# Tut1.net
KiCad netlist of a schematic drawn in Altium Designer
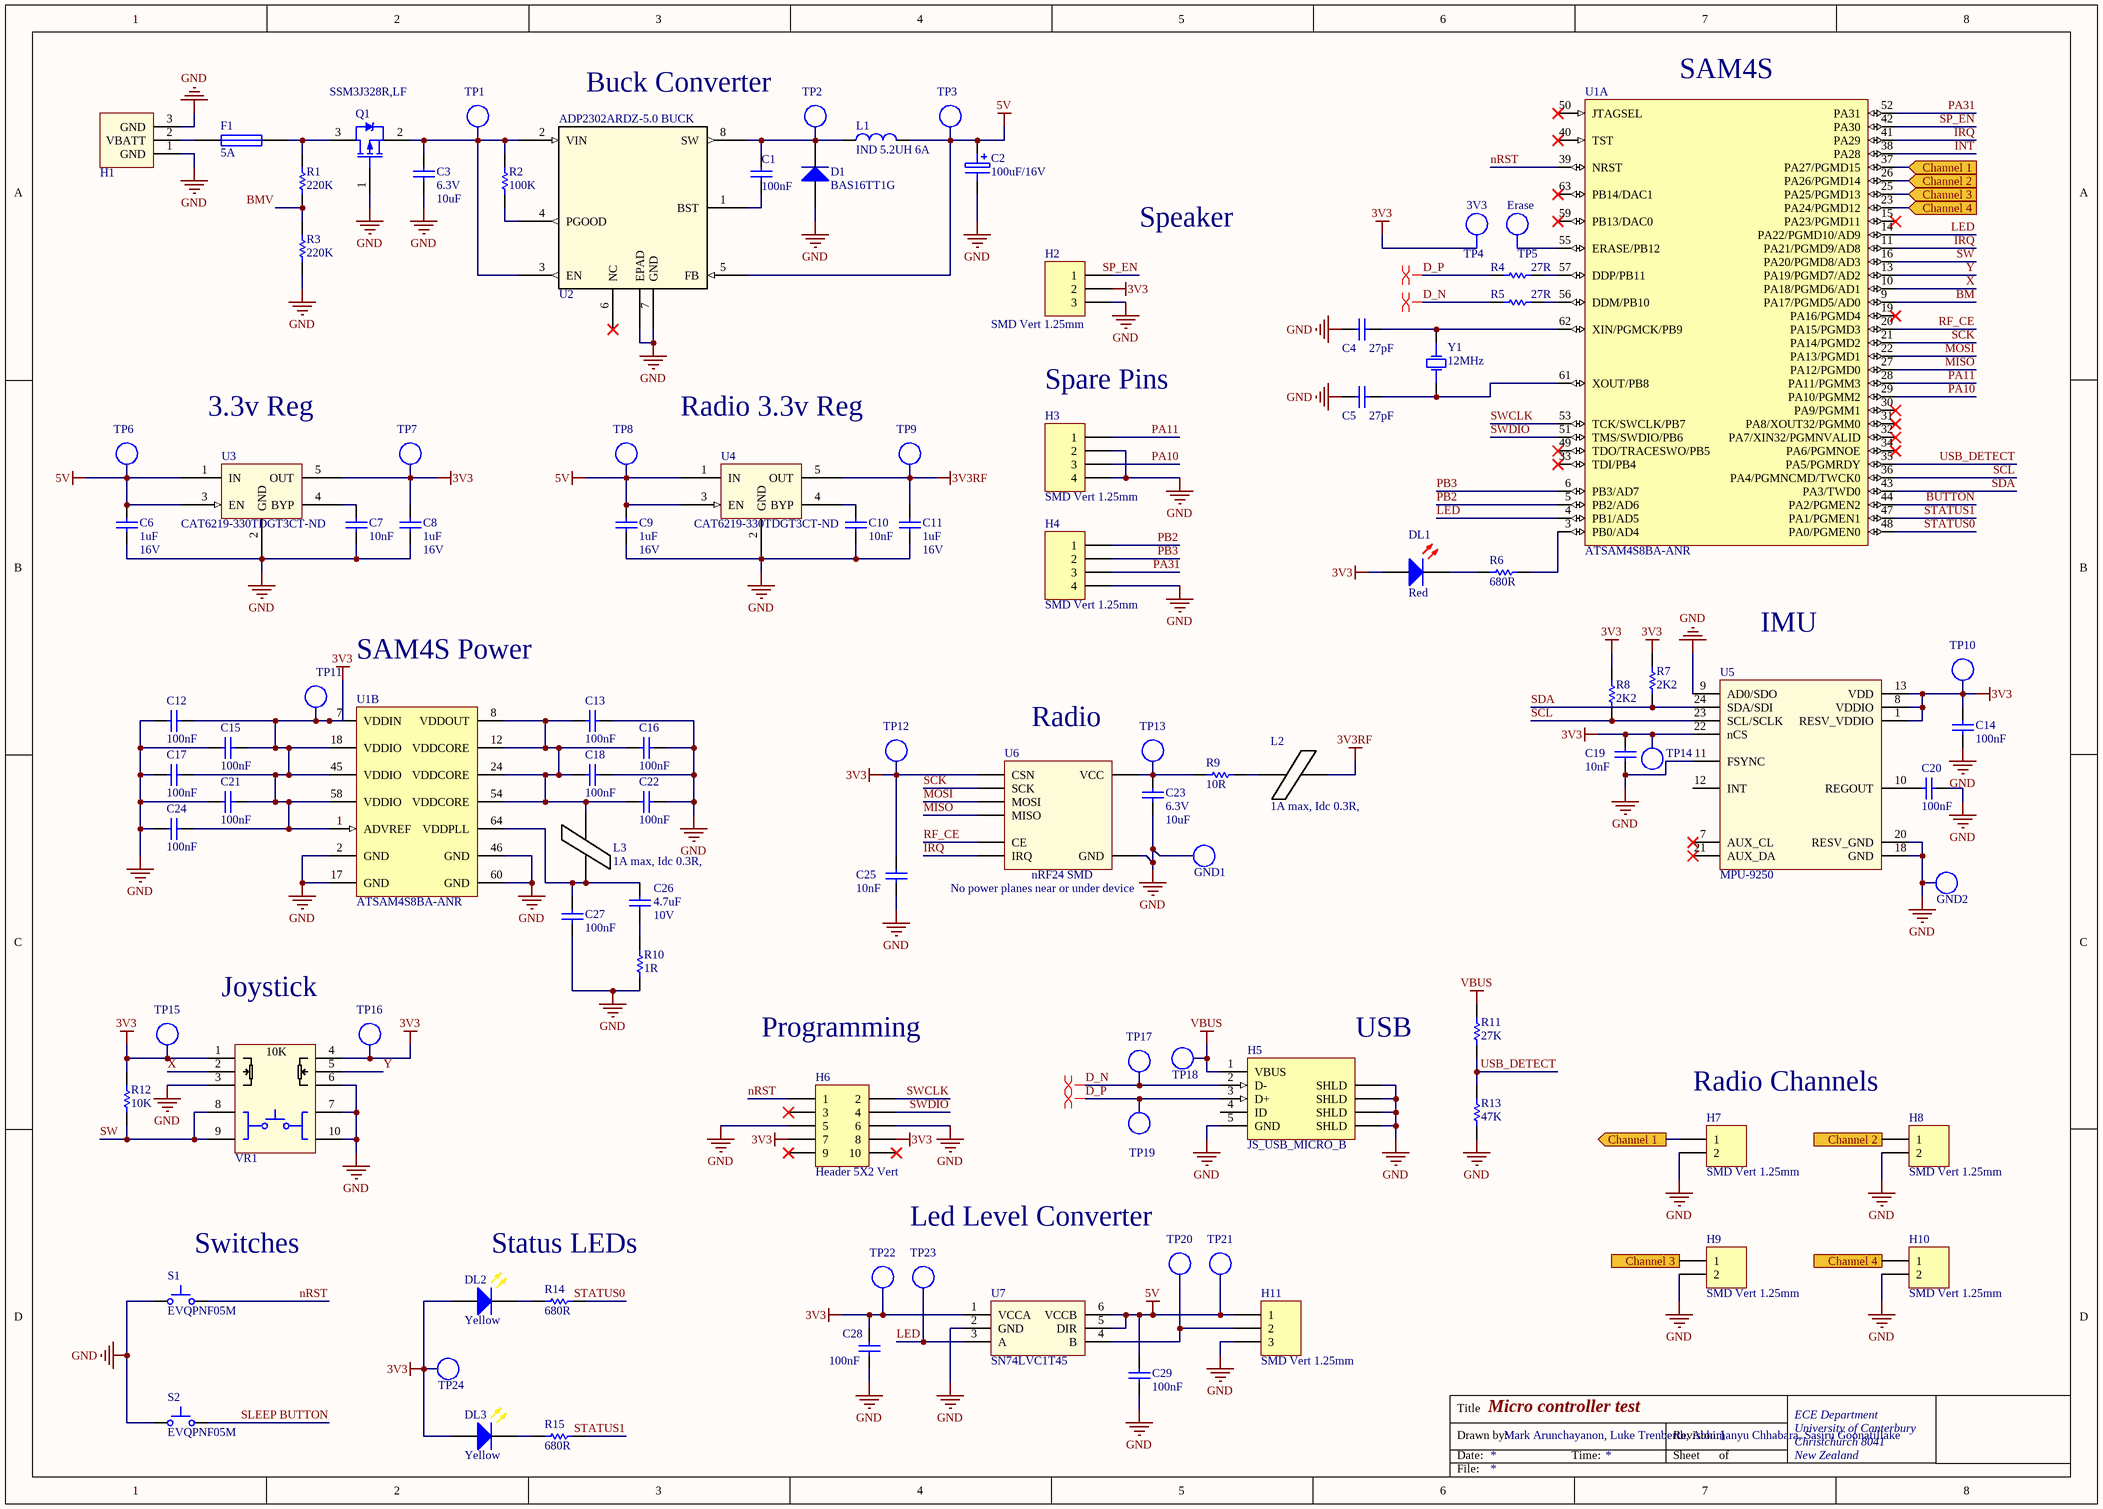
[diagram p0: Tut1.SchDoc]

(export (version "E")
  (design (tool "Eeschema 10.0.6"))
  (components
    (comp (ref "C1")
      (value "100nF")
      (footprint "CAPC1608L")
      (description "CAP CER 100nF X7R +-10% 50V 0603")
      (libsource (lib "ECE AD19Components_19V1") (part "CC_100nF_0603"))
    )
    (comp (ref "C2")
      (value "100uF/16V")
      (footprint "NICH-1")
      (description "CAP ALUM 100uF 16V SMD")
      (fields (field (name "MANUFACTURER") "Nichcon"))
      (libsource (lib "ECE AD19Components_19V1") (part "CA_100uF_16V"))
    )
    (comp (ref "C3")
      (value "10uF")
      (footprint "CAPC1608L")
      (description "CAP CER 10UF X5R +-20% 6V3 0603")
      (fields (field (name "VOLTAGE - RATED") "6.3V"))
      (libsource (lib "ECE AD19Components_19V1") (part "CC_10uF_0603"))
    )
    (comp (ref "C4")
      (value "27pF")
      (footprint "CAPC1608L")
      (description "CAP CER 27pF NPO/COG +-5% 50V 0603")
      (libsource (lib "ECE AD19Components_19V1") (part "CC_27pF_0603"))
    )
    (comp (ref "C5")
      (value "27pF")
      (footprint "CAPC1608L")
      (description "CAP CER 27pF NPO/COG +-5% 50V 0603")
      (libsource (lib "ECE AD19Components_19V1") (part "CC_27pF_0603"))
    )
    (comp (ref "C6")
      (value "1uF")
      (footprint "CAPC1608L")
      (description "CAP CER 1uF Y5V -20% +80% 16V 0603")
      (fields (field (name "MAX VOLTAGE") "16V"))
      (libsource (lib "ECE AD19Components_19V1") (part "CC_1uF_0603"))
    )
    (comp (ref "C7")
      (value "10nF")
      (footprint "CAPC1608L")
      (description "CAP CER 10nF X7R +-10% 50V 0603")
      (libsource (lib "ECE AD19Components_19V1") (part "CC_10nF_0603"))
    )
    (comp (ref "C8")
      (value "1uF")
      (footprint "CAPC1608L")
      (description "CAP CER 1uF Y5V -20% +80% 16V 0603")
      (fields (field (name "MAX VOLTAGE") "16V"))
      (libsource (lib "ECE AD19Components_19V1") (part "CC_1uF_0603"))
    )
    (comp (ref "C9")
      (value "1uF")
      (footprint "CAPC1608L")
      (description "CAP CER 1uF Y5V -20% +80% 16V 0603")
      (fields (field (name "MAX VOLTAGE") "16V"))
      (libsource (lib "ECE AD19Components_19V1") (part "CC_1uF_0603"))
    )
    (comp (ref "C10")
      (value "10nF")
      (footprint "CAPC1608L")
      (description "CAP CER 10nF X7R +-10% 50V 0603")
      (libsource (lib "ECE AD19Components_19V1") (part "CC_10nF_0603"))
    )
    (comp (ref "C11")
      (value "1uF")
      (footprint "CAPC1608L")
      (description "CAP CER 1uF Y5V -20% +80% 16V 0603")
      (fields (field (name "MAX VOLTAGE") "16V"))
      (libsource (lib "ECE AD19Components_19V1") (part "CC_1uF_0603"))
    )
    (comp (ref "C12")
      (value "100nF")
      (footprint "CAPC1608L")
      (description "CAP CER 100nF X7R +-10% 50V 0603")
      (libsource (lib "ECE AD19Components_19V1") (part "CC_100nF_0603"))
    )
    (comp (ref "C13")
      (value "100nF")
      (footprint "CAPC1608L")
      (description "CAP CER 100nF X7R +-10% 50V 0603")
      (libsource (lib "ECE AD19Components_19V1") (part "CC_100nF_0603"))
    )
    (comp (ref "C14")
      (value "100nF")
      (footprint "CAPC1608L")
      (description "CAP CER 100nF X7R +-10% 50V 0603")
      (libsource (lib "ECE AD19Components_19V1") (part "CC_100nF_0603"))
    )
    (comp (ref "C15")
      (value "100nF")
      (footprint "CAPC1608L")
      (description "CAP CER 100nF X7R +-10% 50V 0603")
      (libsource (lib "ECE AD19Components_19V1") (part "CC_100nF_0603"))
    )
    (comp (ref "C16")
      (value "100nF")
      (footprint "CAPC1608L")
      (description "CAP CER 100nF X7R +-10% 50V 0603")
      (libsource (lib "ECE AD19Components_19V1") (part "CC_100nF_0603"))
    )
    (comp (ref "C17")
      (value "100nF")
      (footprint "CAPC1608L")
      (description "CAP CER 100nF X7R +-10% 50V 0603")
      (libsource (lib "ECE AD19Components_19V1") (part "CC_100nF_0603"))
    )
    (comp (ref "C18")
      (value "100nF")
      (footprint "CAPC1608L")
      (description "CAP CER 100nF X7R +-10% 50V 0603")
      (libsource (lib "ECE AD19Components_19V1") (part "CC_100nF_0603"))
    )
    (comp (ref "C19")
      (value "10nF")
      (footprint "CAPC1608L")
      (description "CAP CER 10nF X7R +-10% 50V 0603")
      (libsource (lib "ECE AD19Components_19V1") (part "CC_10nF_0603"))
    )
    (comp (ref "C20")
      (value "100nF")
      (footprint "CAPC1608L")
      (description "CAP CER 100nF X7R +-10% 50V 0603")
      (libsource (lib "ECE AD19Components_19V1") (part "CC_100nF_0603"))
    )
    (comp (ref "C21")
      (value "100nF")
      (footprint "CAPC1608L")
      (description "CAP CER 100nF X7R +-10% 50V 0603")
      (libsource (lib "ECE AD19Components_19V1") (part "CC_100nF_0603"))
    )
    (comp (ref "C22")
      (value "100nF")
      (footprint "CAPC1608L")
      (description "CAP CER 100nF X7R +-10% 50V 0603")
      (libsource (lib "ECE AD19Components_19V1") (part "CC_100nF_0603"))
    )
    (comp (ref "C23")
      (value "10uF")
      (footprint "CAPC1608L")
      (description "CAP CER 10UF X5R +-20% 6V3 0603")
      (fields (field (name "VOLTAGE - RATED") "6.3V"))
      (libsource (lib "ECE AD19Components_19V1") (part "CC_10uF_0603"))
    )
    (comp (ref "C24")
      (value "100nF")
      (footprint "CAPC1608L")
      (description "CAP CER 100nF X7R +-10% 50V 0603")
      (libsource (lib "ECE AD19Components_19V1") (part "CC_100nF_0603"))
    )
    (comp (ref "C25")
      (value "10nF")
      (footprint "CAPC1608L")
      (description "CAP CER 10nF X7R +-10% 50V 0603")
      (libsource (lib "ECE AD19Components_19V1") (part "CC_10nF_0603"))
    )
    (comp (ref "C26")
      (value "4.7uF")
      (footprint "CAPC1608N")
      (description "CAP CER 4.7uF X5R +-20%  10V 0603")
      (fields (field (name "MAX VOLTAGE") "10V"))
      (libsource (lib "ECE AD19Components_19V1") (part "CC_4.7uF_0603"))
    )
    (comp (ref "C27")
      (value "100nF")
      (footprint "CAPC1608L")
      (description "CAP CER 100nF X7R +-10% 50V 0603")
      (libsource (lib "ECE AD19Components_19V1") (part "CC_100nF_0603"))
    )
    (comp (ref "C28")
      (value "100nF")
      (footprint "CAPC1608L")
      (description "CAP CER 100nF X7R +-10% 50V 0603")
      (libsource (lib "ECE AD19Components_19V1") (part "CC_100nF_0603"))
    )
    (comp (ref "C29")
      (value "100nF")
      (footprint "CAPC1608L")
      (description "CAP CER 100nF X7R +-10% 50V 0603")
      (libsource (lib "ECE AD19Components_19V1") (part "CC_100nF_0603"))
    )
    (comp (ref "D1")
      (value "BAS16TT1G")
      (footprint "SOT416")
      (description "Diode Switching, Vr 75V, 200mA, SOT-416")
      (fields (field (name "MANUFACTURER") "ON Semiconductor"))
      (libsource (lib "ECE AD19Components_19V1") (part "DR_BAS16TT1G"))
    )
    (comp (ref "DL1")
      (value "Red")
      (footprint "WL-SMCW0603")
      (description "LED Red 250mcd 0603 SMD")
      (fields
        (field (name "MANUFACTURER") "WURTH ELEKTRONIK")
        (field (name "MANUFACTURER PART NUMBER") "150060RS75000")
        (field (name "LED COLOUR") "Red")
      )
      (libsource (lib "ECE AD19Components_19V1") (part "DL_150060RS75000"))
    )
    (comp (ref "DL2")
      (value "Yellow")
      (footprint "WL-SMCW0603")
      (description "LED Yellow 120mcd 0603 SMD")
      (fields
        (field (name "MANUFACTURER") "WURTH ELEKTRONIK")
        (field (name "MANUFACTURER PART NUMBER") "150060YS75000")
        (field (name "LED COLOUR") "Yellow")
      )
      (libsource (lib "ECE AD19Components_19V1") (part "DL_150060YS75000"))
    )
    (comp (ref "DL3")
      (value "Yellow")
      (footprint "WL-SMCW0603")
      (description "LED Yellow 120mcd 0603 SMD")
      (fields
        (field (name "MANUFACTURER") "WURTH ELEKTRONIK")
        (field (name "MANUFACTURER PART NUMBER") "150060YS75000")
        (field (name "LED COLOUR") "Yellow")
      )
      (libsource (lib "ECE AD19Components_19V1") (part "DL_150060YS75000"))
    )
    (comp (ref "F1")
      (value "5A")
      (footprint "RESC3216N")
      (description "Fuse 5.0A Fast Acting 1206 SMD")
      (fields (field (name "MANUFACTURER PART NUMBER") "C1F5") (field (name "MANUFACTURER") "Bel TRP"))
      (libsource (lib "ECE AD19Components_19V1") (part "FS_Fuse_5.0A"))
    )
    (comp (ref "GND1")
      (value "TP_0603")
      (footprint "TP_0603")
      (description "Test Point 1.65X0.9X1.2mm SMD")
      (fields
        (field (name "MANUFACTURER") "TE Connectivity AMP Connectors")
        (field (name "MANUFACTURER PART NUMBER") "1625854-3")
      )
      (libsource (lib "ECE AD19Components_19V1") (part "TP_0603"))
    )
    (comp (ref "GND2")
      (value "TP_0603")
      (footprint "TP_0603")
      (description "Test Point 1.65X0.9X1.2mm SMD")
      (fields
        (field (name "MANUFACTURER") "TE Connectivity AMP Connectors")
        (field (name "MANUFACTURER PART NUMBER") "1625854-3")
      )
      (libsource (lib "ECE AD19Components_19V1") (part "TP_0603"))
    )
    (comp (ref "H1")
      (value "Battery_HEADER_3pin")
      (footprint "BATT_HEADER_3POS")
      (description "3Pin Header 2.54mm spacing")
      (libsource (lib "ENCE461AD19_19V2") (part "Battery_HEADER_3pin"))
    )
    (comp (ref "H2")
      (value "SMD Vert 1.25mm")
      (footprint "SD-53398-0319")
      (description "Header_Vert_3Pos_1.25mm_125V@1A_SMT")
      (fields (field (name "MANUFACTURER") "MOLEX") (field (name "MANUFACTURER PART NUMBER") "53398-0371"))
      (libsource (lib "ECE AD19Components_19V1") (part "JB_53398-03"))
    )
    (comp (ref "H3")
      (value "SMD Vert 1.25mm")
      (footprint "SD-53398-0419")
      (description "Header_Vert_4Pos_1.25mm_125V@1A_SMT")
      (fields (field (name "MANUFACTURER") "MOLEX") (field (name "MANUFACTURER PART NUMBER") "53398-0471"))
      (libsource (lib "ECE AD19Components_19V1") (part "JB_53398-04"))
    )
    (comp (ref "H4")
      (value "SMD Vert 1.25mm")
      (footprint "SD-53398-0419")
      (description "Header_Vert_4Pos_1.25mm_125V@1A_SMT")
      (fields (field (name "MANUFACTURER") "MOLEX") (field (name "MANUFACTURER PART NUMBER") "53398-0471"))
      (libsource (lib "ECE AD19Components_19V1") (part "JB_53398-04"))
    )
    (comp (ref "H5")
      (value "JS_USB_MICRO_B")
      (footprint "FCI_USB_10118194-0001LF")
      (description "CONN USB MICRO B RECPT SMT R/A")
      (fields (field (name "MANUFACTURER") "FCI") (field (name "MANUFACTURER PART NUMBER") "10118194-0001LF"))
      (libsource (lib "ECE AD19Components_19V1") (part "JS_USB_MICRO_B_SMT"))
    )
    (comp (ref "H6")
      (value "Header 5X2 Vert")
      (footprint "IDC2.54-V10D")
      (description "IDC Header, 2,54mm, 10-Pin, Vert")
      (libsource (lib "ECE AD19Components_19V1") (part "JA_HDR_IDC_5X2_VERT"))
    )
    (comp (ref "H7")
      (value "SMD Vert 1.25mm")
      (footprint "SD-53398-0219")
      (description "Header_Vert_2Pos_1.25mm_125V@1A_SMT")
      (fields
        (field (name "MANUFACTURER") "Molex Inc")
        (field (name "MANUFACTURER PART NUMBER") "0533980271")
      )
      (libsource (lib "ECE AD19Components_19V1") (part "JB_53398-02"))
    )
    (comp (ref "H8")
      (value "SMD Vert 1.25mm")
      (footprint "SD-53398-0219")
      (description "Header_Vert_2Pos_1.25mm_125V@1A_SMT")
      (fields
        (field (name "MANUFACTURER") "Molex Inc")
        (field (name "MANUFACTURER PART NUMBER") "0533980271")
      )
      (libsource (lib "ECE AD19Components_19V1") (part "JB_53398-02"))
    )
    (comp (ref "H9")
      (value "SMD Vert 1.25mm")
      (footprint "SD-53398-0219")
      (description "Header_Vert_2Pos_1.25mm_125V@1A_SMT")
      (fields
        (field (name "MANUFACTURER") "Molex Inc")
        (field (name "MANUFACTURER PART NUMBER") "0533980271")
      )
      (libsource (lib "ECE AD19Components_19V1") (part "JB_53398-02"))
    )
    (comp (ref "H10")
      (value "SMD Vert 1.25mm")
      (footprint "SD-53398-0219")
      (description "Header_Vert_2Pos_1.25mm_125V@1A_SMT")
      (fields
        (field (name "MANUFACTURER") "Molex Inc")
        (field (name "MANUFACTURER PART NUMBER") "0533980271")
      )
      (libsource (lib "ECE AD19Components_19V1") (part "JB_53398-02"))
    )
    (comp (ref "H11")
      (value "SMD Vert 1.25mm")
      (footprint "SD-53398-0319")
      (description "Header_Vert_3Pos_1.25mm_125V@1A_SMT")
      (fields (field (name "MANUFACTURER") "MOLEX") (field (name "MANUFACTURER PART NUMBER") "53398-0371"))
      (libsource (lib "") (part "JB_53398-03_1"))
    )
    (comp (ref "L1")
      (value "IND 5.2UH 6A")
      (footprint "INDUCTOR5u2")
      (description "FIXED IND 5.2UH 6A 22 MOHM SMD")
      (fields
        (field (name "MANUFACTURER") "Sumida America Components Inc.")
        (field (name "MANUFACTURER PART NUMBER") "CDRH104RNP-5R2NC")
      )
      (libsource (lib "ENCE461AD19_19V2") (part "CDRH104RNP-5R2NC"))
    )
    (comp (ref "L2")
      (value "1A max, Idc 0.3R,")
      (footprint "INDC3216L")
      (description "Ferrite Bead, Rdc 0.3R, Z100MHZ 600R, Imax 1A, SMD 1206")
      (fields
        (field (name "MANUFACTURER") "FAIR-RITE")
        (field (name "MANUFACTURER PART NUMBER") "2512066017Y1")
      )
      (libsource (lib "ECE AD19Components_19V1") (part "IN_Ferrite-Bead"))
    )
    (comp (ref "L3")
      (value "1A max, Idc 0.3R,")
      (footprint "INDC3216L")
      (description "Ferrite Bead, Rdc 0.3R, Z100MHZ 600R, Imax 1A, SMD 1206")
      (fields
        (field (name "MANUFACTURER") "FAIR-RITE")
        (field (name "MANUFACTURER PART NUMBER") "2512066017Y1")
      )
      (libsource (lib "ECE AD19Components_19V1") (part "IN_Ferrite-Bead"))
    )
    (comp (ref "Q1")
      (value "SSM3J328R,LF")
      (footprint "SOT23_L")
      (description "MOSFET P-CH 20V 6A SOT23-3")
      (fields
        (field (name "MANUFACTURER") "Toshiba")
        (field (name "MANUFACTURER PART NUMBER") "SSM3J328R,LF")
      )
      (libsource (lib "ECE AD19Components_19V1") (part "TM_SSM3J328R"))
    )
    (comp (ref "R1")
      (value "220K")
      (footprint "RESC1608L")
      (description "RES 3.3K OHM 1/10W 5% 0603 SMD")
      (libsource (lib "ECE AD19Components_19V1") (part "RS_220K"))
    )
    (comp (ref "R2")
      (value "100K")
      (footprint "RESC1608L")
      (description "RES 100K OHM 1/10W 5% 0603 SMD")
      (libsource (lib "ECE AD19Components_19V1") (part "RS_100K"))
    )
    (comp (ref "R3")
      (value "220K")
      (footprint "RESC1608L")
      (description "RES 3.3K OHM 1/10W 5% 0603 SMD")
      (libsource (lib "ECE AD19Components_19V1") (part "RS_220K"))
    )
    (comp (ref "R4")
      (value "27R")
      (footprint "RESC3216L")
      (description "RES 27R OHM 1/4W 5% 1206 SMD")
      (libsource (lib "ECE AD19Components_19V1") (part "RT_27R"))
    )
    (comp (ref "R5")
      (value "27R")
      (footprint "RESC3216L")
      (description "RES 27R OHM 1/4W 5% 1206 SMD")
      (libsource (lib "ECE AD19Components_19V1") (part "RT_27R"))
    )
    (comp (ref "R6")
      (value "680R")
      (footprint "RESC1608L")
      (description "RES 680 OHM 1/10W 5% 0603 SMD")
      (libsource (lib "ECE AD19Components_19V1") (part "RS_680R"))
    )
    (comp (ref "R7")
      (value "2K2")
      (footprint "RESC1608L")
      (description "RES 2.2K OHM 1/10W 5% 0603 SMD")
      (libsource (lib "ECE AD19Components_19V1") (part "RS_2K2"))
    )
    (comp (ref "R8")
      (value "2K2")
      (footprint "RESC1608L")
      (description "RES 2.2K OHM 1/10W 5% 0603 SMD")
      (libsource (lib "ECE AD19Components_19V1") (part "RS_2K2"))
    )
    (comp (ref "R9")
      (value "10R")
      (footprint "RESC1608L")
      (description "RES 10 OHM 1/10W 5% 0603 SMD")
      (libsource (lib "ECE AD19Components_19V1") (part "RS_10R"))
    )
    (comp (ref "R10")
      (value "1R")
      (footprint "RESC3216L")
      (description "RES 1R OHM 1/4W 5% 1206 SMD")
      (libsource (lib "ECE AD19Components_19V1") (part "RT_1R"))
    )
    (comp (ref "R11")
      (value "27K")
      (footprint "RESC1608L")
      (description "RES 27K OHM 1/10W 5% 0603 SMD")
      (libsource (lib "ECE AD19Components_19V1") (part "RS_27K"))
    )
    (comp (ref "R12")
      (value "10K")
      (footprint "RESC1608L")
      (description "RES 10.0K OHM 1/10W 5% 0603 SMD")
      (libsource (lib "ECE AD19Components_19V1") (part "RS_10K"))
    )
    (comp (ref "R13")
      (value "47K")
      (footprint "RESC1608N")
      (description "RES 47.0K OHM 1/10W 5% 0603 SMD")
      (libsource (lib "ECE AD19Components_19V1") (part "RS_47K"))
    )
    (comp (ref "R14")
      (value "680R")
      (footprint "RESC1608L")
      (description "RES 680 OHM 1/10W 5% 0603 SMD")
      (libsource (lib "ECE AD19Components_19V1") (part "RS_680R"))
    )
    (comp (ref "R15")
      (value "680R")
      (footprint "RESC1608L")
      (description "RES 680 OHM 1/10W 5% 0603 SMD")
      (libsource (lib "ECE AD19Components_19V1") (part "RS_680R"))
    )
    (comp (ref "S1")
      (value "EVQPNF05M")
      (footprint "EVQPNF05M")
      (description "Panasonic 6 x 3.5mm SMD Light Touch Switch Type SMD")
      (fields (field (name "MANUFACTURER") "Panasonic"))
      (libsource (lib "ECE AD19Components_19V1") (part "WS_EVQPNF05M"))
    )
    (comp (ref "S2")
      (value "EVQPNF05M")
      (footprint "EVQPNF05M")
      (description "Panasonic 6 x 3.5mm SMD Light Touch Switch Type SMD")
      (fields (field (name "MANUFACTURER") "Panasonic"))
      (libsource (lib "ECE AD19Components_19V1") (part "WS_EVQPNF05M"))
    )
    (comp (ref "TP1")
      (value "TP_0603")
      (footprint "TP_0603")
      (description "Test Point 1.65X0.9X1.2mm SMD")
      (fields
        (field (name "MANUFACTURER") "TE Connectivity AMP Connectors")
        (field (name "MANUFACTURER PART NUMBER") "1625854-3")
      )
      (libsource (lib "ECE AD19Components_19V1") (part "TP_0603"))
    )
    (comp (ref "TP2")
      (value "TP_0603")
      (footprint "TP_0603")
      (description "Test Point 1.65X0.9X1.2mm SMD")
      (fields
        (field (name "MANUFACTURER") "TE Connectivity AMP Connectors")
        (field (name "MANUFACTURER PART NUMBER") "1625854-3")
      )
      (libsource (lib "ECE AD19Components_19V1") (part "TP_0603"))
    )
    (comp (ref "TP3")
      (value "TP_0603")
      (footprint "TP_0603")
      (description "Test Point 1.65X0.9X1.2mm SMD")
      (fields
        (field (name "MANUFACTURER") "TE Connectivity AMP Connectors")
        (field (name "MANUFACTURER PART NUMBER") "1625854-3")
      )
      (libsource (lib "ECE AD19Components_19V1") (part "TP_0603"))
    )
    (comp (ref "TP4")
      (value "3V3")
      (footprint "TP_1206")
      (description "Test-Point 3.3x1.6x2.1mm SMD")
      (fields
        (field (name "MANUFACTURER") "Harwin Inc")
        (field (name "MANUFACTURER PART NUMBER") "S1751-46R")
      )
      (libsource (lib "ECE AD19Components_19V1") (part "TP_1206"))
    )
    (comp (ref "TP5")
      (value "Erase")
      (footprint "TP_1206")
      (description "Test-Point 3.3x1.6x2.1mm SMD")
      (fields
        (field (name "MANUFACTURER") "Harwin Inc")
        (field (name "MANUFACTURER PART NUMBER") "S1751-46R")
      )
      (libsource (lib "ECE AD19Components_19V1") (part "TP_1206"))
    )
    (comp (ref "TP6")
      (value "TP_0603")
      (footprint "TP_0603")
      (description "Test Point 1.65X0.9X1.2mm SMD")
      (fields
        (field (name "MANUFACTURER") "TE Connectivity AMP Connectors")
        (field (name "MANUFACTURER PART NUMBER") "1625854-3")
      )
      (libsource (lib "ECE AD19Components_19V1") (part "TP_0603"))
    )
    (comp (ref "TP7")
      (value "TP_0603")
      (footprint "TP_0603")
      (description "Test Point 1.65X0.9X1.2mm SMD")
      (fields
        (field (name "MANUFACTURER") "TE Connectivity AMP Connectors")
        (field (name "MANUFACTURER PART NUMBER") "1625854-3")
      )
      (libsource (lib "ECE AD19Components_19V1") (part "TP_0603"))
    )
    (comp (ref "TP8")
      (value "TP_0603")
      (footprint "TP_0603")
      (description "Test Point 1.65X0.9X1.2mm SMD")
      (fields
        (field (name "MANUFACTURER") "TE Connectivity AMP Connectors")
        (field (name "MANUFACTURER PART NUMBER") "1625854-3")
      )
      (libsource (lib "ECE AD19Components_19V1") (part "TP_0603"))
    )
    (comp (ref "TP9")
      (value "TP_0603")
      (footprint "TP_0603")
      (description "Test Point 1.65X0.9X1.2mm SMD")
      (fields
        (field (name "MANUFACTURER") "TE Connectivity AMP Connectors")
        (field (name "MANUFACTURER PART NUMBER") "1625854-3")
      )
      (libsource (lib "ECE AD19Components_19V1") (part "TP_0603"))
    )
    (comp (ref "TP10")
      (value "TP_0603")
      (footprint "TP_0603")
      (description "Test Point 1.65X0.9X1.2mm SMD")
      (fields
        (field (name "MANUFACTURER") "TE Connectivity AMP Connectors")
        (field (name "MANUFACTURER PART NUMBER") "1625854-3")
      )
      (libsource (lib "ECE AD19Components_19V1") (part "TP_0603"))
    )
    (comp (ref "TP11")
      (value "TP_0603")
      (footprint "TP_0603")
      (description "Test Point 1.65X0.9X1.2mm SMD")
      (fields
        (field (name "MANUFACTURER") "TE Connectivity AMP Connectors")
        (field (name "MANUFACTURER PART NUMBER") "1625854-3")
      )
      (libsource (lib "ECE AD19Components_19V1") (part "TP_0603"))
    )
    (comp (ref "TP12")
      (value "TP_0603")
      (footprint "TP_0603")
      (description "Test Point 1.65X0.9X1.2mm SMD")
      (fields
        (field (name "MANUFACTURER") "TE Connectivity AMP Connectors")
        (field (name "MANUFACTURER PART NUMBER") "1625854-3")
      )
      (libsource (lib "ECE AD19Components_19V1") (part "TP_0603"))
    )
    (comp (ref "TP13")
      (value "TP_0603")
      (footprint "TP_0603")
      (description "Test Point 1.65X0.9X1.2mm SMD")
      (fields
        (field (name "MANUFACTURER") "TE Connectivity AMP Connectors")
        (field (name "MANUFACTURER PART NUMBER") "1625854-3")
      )
      (libsource (lib "ECE AD19Components_19V1") (part "TP_0603"))
    )
    (comp (ref "TP14")
      (value "TP_0603")
      (footprint "TP_0603")
      (description "Test Point 1.65X0.9X1.2mm SMD")
      (fields
        (field (name "MANUFACTURER") "TE Connectivity AMP Connectors")
        (field (name "MANUFACTURER PART NUMBER") "1625854-3")
      )
      (libsource (lib "ECE AD19Components_19V1") (part "TP_0603"))
    )
    (comp (ref "TP15")
      (value "TP_0603")
      (footprint "TP_0603")
      (description "Test Point 1.65X0.9X1.2mm SMD")
      (fields
        (field (name "MANUFACTURER") "TE Connectivity AMP Connectors")
        (field (name "MANUFACTURER PART NUMBER") "1625854-3")
      )
      (libsource (lib "ECE AD19Components_19V1") (part "TP_0603"))
    )
    (comp (ref "TP16")
      (value "TP_0603")
      (footprint "TP_0603")
      (description "Test Point 1.65X0.9X1.2mm SMD")
      (fields
        (field (name "MANUFACTURER") "TE Connectivity AMP Connectors")
        (field (name "MANUFACTURER PART NUMBER") "1625854-3")
      )
      (libsource (lib "ECE AD19Components_19V1") (part "TP_0603"))
    )
    (comp (ref "TP17")
      (value "TP_0603")
      (footprint "TP_0603")
      (description "Test Point 1.65X0.9X1.2mm SMD")
      (fields
        (field (name "MANUFACTURER") "TE Connectivity AMP Connectors")
        (field (name "MANUFACTURER PART NUMBER") "1625854-3")
      )
      (libsource (lib "ECE AD19Components_19V1") (part "TP_0603"))
    )
    (comp (ref "TP18")
      (value "TP_0603")
      (footprint "TP_0603")
      (description "Test Point 1.65X0.9X1.2mm SMD")
      (fields
        (field (name "MANUFACTURER") "TE Connectivity AMP Connectors")
        (field (name "MANUFACTURER PART NUMBER") "1625854-3")
      )
      (libsource (lib "ECE AD19Components_19V1") (part "TP_0603"))
    )
    (comp (ref "TP19")
      (value "TP_0603")
      (footprint "TP_0603")
      (description "Test Point 1.65X0.9X1.2mm SMD")
      (fields
        (field (name "MANUFACTURER") "TE Connectivity AMP Connectors")
        (field (name "MANUFACTURER PART NUMBER") "1625854-3")
      )
      (libsource (lib "ECE AD19Components_19V1") (part "TP_0603"))
    )
    (comp (ref "TP20")
      (value "TP_0603")
      (footprint "TP_0603")
      (description "Test Point 1.65X0.9X1.2mm SMD")
      (fields
        (field (name "MANUFACTURER") "TE Connectivity AMP Connectors")
        (field (name "MANUFACTURER PART NUMBER") "1625854-3")
      )
      (libsource (lib "ECE AD19Components_19V1") (part "TP_0603"))
    )
    (comp (ref "TP21")
      (value "TP_0603")
      (footprint "TP_0603")
      (description "Test Point 1.65X0.9X1.2mm SMD")
      (fields
        (field (name "MANUFACTURER") "TE Connectivity AMP Connectors")
        (field (name "MANUFACTURER PART NUMBER") "1625854-3")
      )
      (libsource (lib "ECE AD19Components_19V1") (part "TP_0603"))
    )
    (comp (ref "TP22")
      (value "TP_0603")
      (footprint "TP_0603")
      (description "Test Point 1.65X0.9X1.2mm SMD")
      (fields
        (field (name "MANUFACTURER") "TE Connectivity AMP Connectors")
        (field (name "MANUFACTURER PART NUMBER") "1625854-3")
      )
      (libsource (lib "ECE AD19Components_19V1") (part "TP_0603"))
    )
    (comp (ref "TP23")
      (value "TP_0603")
      (footprint "TP_0603")
      (description "Test Point 1.65X0.9X1.2mm SMD")
      (fields
        (field (name "MANUFACTURER") "TE Connectivity AMP Connectors")
        (field (name "MANUFACTURER PART NUMBER") "1625854-3")
      )
      (libsource (lib "ECE AD19Components_19V1") (part "TP_0603"))
    )
    (comp (ref "TP24")
      (value "TP_0603")
      (footprint "TP_0603")
      (description "Test Point 1.65X0.9X1.2mm SMD")
      (fields
        (field (name "MANUFACTURER") "TE Connectivity AMP Connectors")
        (field (name "MANUFACTURER PART NUMBER") "1625854-3")
      )
      (libsource (lib "ECE AD19Components_19V1") (part "TP_0603"))
    )
    (comp (ref "U1")
      (value "ATSAM4S8BA-ANR")
      (footprint "LQFP64_L")
      (description "IC MCU 32BIT 512KB FLASH 64LQFP")
      (fields (field (name "MANUFACTURER") "Atmel"))
      (libsource (lib "ECE AD19Components_19V1") (part "SE_ATSAM4S16BA-MU"))
    )
    (comp (ref "U2")
      (value "ADP2302ARDZ-5.0 BUCK")
      (footprint "RD_8_1")
      (description "IC REG BUCK 5V 2A 8SOIC")
      (fields (field (name "MANUFACTURER_PART_NUMBER") "ADP2302ARDZ-5.0-R7"))
      (libsource (lib "ENCE461AD19_19V2") (part "ADP2302ARDZ-5.0-R7"))
    )
    (comp (ref "U3")
      (value "CAT6219-330TDGT3")
      (footprint "SOT95P280X145-5N")
      (description "IC REG LIN 3.3V 500MA TSOT23-5")
      (fields
        (field (name "BASE PART NUMBER") "CAT6219")
        (field (name "SUPPLIER PART NUMBER") "CAT6219-330TDGT3CT-ND")
      )
      (libsource (lib "ENCE461AD19_19V2") (part "SV_CAT6219-330TDGT3"))
    )
    (comp (ref "U4")
      (value "CAT6219-330TDGT3")
      (footprint "SOT95P280X145-5N")
      (description "IC REG LIN 3.3V 500MA TSOT23-5")
      (fields
        (field (name "BASE PART NUMBER") "CAT6219")
        (field (name "SUPPLIER PART NUMBER") "CAT6219-330TDGT3CT-ND")
      )
      (libsource (lib "ENCE461AD19_19V2") (part "SV_CAT6219-330TDGT3"))
    )
    (comp (ref "U5")
      (value "MPU-9250")
      (footprint "Quad24")
      (description "9 axis IMU")
      (libsource (lib "ENCE461AD19_19V2") (part "MPU-9250"))
    )
    (comp (ref "U6")
      (value "nRF24 SMD")
      (footprint "NRF24")
      (description "nRF24 SMD Module")
      (fields (field (name "WARNING") "No power planes near or under device"))
      (libsource (lib "ENCE461AD19_19V2") (part "NRF24"))
    )
    (comp (ref "U7")
      (value "SN74LVC1T45")
      (footprint "SOT23-6_N")
      (description "1.8V - 5V level converter")
      (libsource (lib "ENCE461_extras_2020") (part "SN74LVC1T45"))
    )
    (comp (ref "VR1")
      (value "Joystick 10k with Sw")
      (footprint "Joystick_Sw")
      (description "JOYSTICK 10K OHM 2 AXIS TH")
      (libsource (lib "ENCE461AD19_19V2") (part "Joystick 10k with Sw"))
    )
    (comp (ref "Y1")
      (value "12MHz")
      (footprint "HC49/4h_SMX")
      (description "12.00 MHZ 18PF HC49/4H SMD")
      (fields (field (name "MANUFACTURER") "Abracon Corporation"))
      (libsource (lib "ECE AD19Components_19V1") (part "XT_CRYSTAL_12MHz"))
    )
  )
  (nets
    (net (code "1") (name "/BM") (class "Default")
      (node (ref "U1") (pin "9") (pinfunction "PA17/PGMD5/AD0_9") (pintype "bidirectional"))
    )
    (net (code "2") (name "/BMV") (class "Default")
      (node (ref "R1") (pin "1") (pinfunction "1_1") (pintype "passive"))
      (node (ref "R3") (pin "2") (pinfunction "2_2") (pintype "passive"))
    )
    (net (code "3") (name "/BUTTON") (class "Default")
      (node (ref "U1") (pin "44") (pinfunction "PA2/PGMEN2_44") (pintype "bidirectional"))
    )
    (net (code "4") (name "/Channel 1") (class "Default")
      (node (ref "H7") (pin "1") (pinfunction "1_1") (pintype "passive"))
      (node (ref "U1") (pin "37") (pinfunction "PA27/PGMD15_37") (pintype "bidirectional"))
    )
    (net (code "5") (name "/Channel 2") (class "Default")
      (node (ref "H8") (pin "1") (pinfunction "1_1") (pintype "passive"))
      (node (ref "U1") (pin "26") (pinfunction "PA26/PGMD14_26") (pintype "bidirectional"))
    )
    (net (code "6") (name "/Channel 3") (class "Default")
      (node (ref "H9") (pin "1") (pinfunction "1_1") (pintype "passive"))
      (node (ref "U1") (pin "25") (pinfunction "PA25/PGMD13_25") (pintype "bidirectional"))
    )
    (net (code "7") (name "/Channel 4") (class "Default")
      (node (ref "H10") (pin "1") (pinfunction "1_1") (pintype "passive"))
      (node (ref "U1") (pin "23") (pinfunction "PA24/PGMD12_23") (pintype "bidirectional"))
    )
    (net (code "8") (name "/D_N") (class "Default")
      (node (ref "H5") (pin "2") (pinfunction "D-_2") (pintype "input"))
      (node (ref "R5") (pin "1") (pinfunction "1_1") (pintype "passive"))
      (node (ref "TP17") (pin "1") (pinfunction "TP_1") (pintype "passive"))
    )
    (net (code "9") (name "/D_P") (class "Default")
      (node (ref "H5") (pin "3") (pinfunction "D+_3") (pintype "input"))
      (node (ref "R4") (pin "1") (pinfunction "1_1") (pintype "passive"))
      (node (ref "TP19") (pin "1") (pinfunction "TP_1") (pintype "passive"))
    )
    (net (code "10") (name "/INT") (class "Default")
      (node (ref "U1") (pin "38") (pinfunction "PA28_38") (pintype "bidirectional"))
    )
    (net (code "11") (name "/IRQ") (class "Default")
      (node (ref "U1") (pin "11") (pinfunction "PA21/PGMD9/AD8_11") (pintype "bidirectional"))
      (node (ref "U1") (pin "41") (pinfunction "PA29_41") (pintype "bidirectional"))
      (node (ref "U6") (pin "8") (pinfunction "IRQ_8") (pintype "passive"))
    )
    (net (code "12") (name "/LED") (class "Default")
      (node (ref "TP23") (pin "1") (pinfunction "TP_1") (pintype "passive"))
      (node (ref "U1") (pin "14") (pinfunction "PA22/PGMD10/AD9_14") (pintype "bidirectional"))
      (node (ref "U1") (pin "4") (pinfunction "PB1/AD5_4") (pintype "bidirectional"))
      (node (ref "U7") (pin "3") (pinfunction "A_3") (pintype "passive"))
    )
    (net (code "13") (name "/MISO") (class "Default")
      (node (ref "U1") (pin "27") (pinfunction "PA12/PGMD0_27") (pintype "bidirectional"))
      (node (ref "U6") (pin "7") (pinfunction "MISO_7") (pintype "passive"))
    )
    (net (code "14") (name "/MOSI") (class "Default")
      (node (ref "U1") (pin "22") (pinfunction "PA13/PGMD1_22") (pintype "bidirectional"))
      (node (ref "U6") (pin "6") (pinfunction "MOSI_6") (pintype "passive"))
    )
    (net (code "15") (name "/PA10") (class "Default")
      (node (ref "H3") (pin "3") (pinfunction "3_3") (pintype "passive"))
      (node (ref "U1") (pin "29") (pinfunction "PA10/PGMM2_29") (pintype "bidirectional"))
    )
    (net (code "16") (name "/PA11") (class "Default")
      (node (ref "H3") (pin "1") (pinfunction "1_1") (pintype "passive"))
      (node (ref "U1") (pin "28") (pinfunction "PA11/PGMM3_28") (pintype "bidirectional"))
    )
    (net (code "17") (name "/PA31") (class "Default")
      (node (ref "H4") (pin "3") (pinfunction "3_3") (pintype "passive"))
      (node (ref "U1") (pin "52") (pinfunction "PA31_52") (pintype "bidirectional"))
    )
    (net (code "18") (name "/PB2") (class "Default")
      (node (ref "H4") (pin "1") (pinfunction "1_1") (pintype "passive"))
      (node (ref "U1") (pin "5") (pinfunction "PB2/AD6_5") (pintype "bidirectional"))
    )
    (net (code "19") (name "/PB3") (class "Default")
      (node (ref "H4") (pin "2") (pinfunction "2_2") (pintype "passive"))
      (node (ref "U1") (pin "6") (pinfunction "PB3/AD7_6") (pintype "bidirectional"))
    )
    (net (code "20") (name "/RF_CE") (class "Default")
      (node (ref "U1") (pin "20") (pinfunction "PA15/PGMD3_20") (pintype "bidirectional"))
      (node (ref "U6") (pin "3") (pinfunction "CE_3") (pintype "passive"))
    )
    (net (code "21") (name "/SCK") (class "Default")
      (node (ref "U1") (pin "21") (pinfunction "PA14/PGMD2_21") (pintype "bidirectional"))
      (node (ref "U6") (pin "5") (pinfunction "SCK_5") (pintype "passive"))
    )
    (net (code "22") (name "/SCL") (class "Default")
      (node (ref "R8") (pin "1") (pinfunction "1_1") (pintype "passive"))
      (node (ref "U1") (pin "36") (pinfunction "PA4/PGMNCMD/TWCK0_36") (pintype "bidirectional"))
      (node (ref "U5") (pin "23") (pinfunction "SCL/SCLK_23") (pintype "passive"))
    )
    (net (code "23") (name "/SDA") (class "Default")
      (node (ref "R7") (pin "1") (pinfunction "1_1") (pintype "passive"))
      (node (ref "U1") (pin "43") (pinfunction "PA3/TWD0_43") (pintype "bidirectional"))
      (node (ref "U5") (pin "24") (pinfunction "SDA/SDI_24") (pintype "passive"))
    )
    (net (code "24") (name "/SLEEP BUTTON") (class "Default") (node (ref "S2") (pin "2") (pintype "passive")))
    (net (code "25") (name "/SP_EN") (class "Default")
      (node (ref "H2") (pin "1") (pinfunction "1_1") (pintype "passive"))
      (node (ref "U1") (pin "42") (pinfunction "PA30_42") (pintype "bidirectional"))
    )
    (net (code "26") (name "/STATUS0") (class "Default")
      (node (ref "R14") (pin "2") (pinfunction "2_2") (pintype "passive"))
      (node (ref "U1") (pin "48") (pinfunction "PA0/PGMEN0_48") (pintype "bidirectional"))
    )
    (net (code "27") (name "/STATUS1") (class "Default")
      (node (ref "R15") (pin "2") (pinfunction "2_2") (pintype "passive"))
      (node (ref "U1") (pin "47") (pinfunction "PA1/PGMEN1_47") (pintype "bidirectional"))
    )
    (net (code "28") (name "/SW") (class "Default")
      (node (ref "R12") (pin "1") (pinfunction "1_1") (pintype "passive"))
      (node (ref "U1") (pin "16") (pinfunction "PA20/PGMD8/AD3_16") (pintype "bidirectional"))
      (node (ref "VR1") (pin "8") (pinfunction "8_8") (pintype "passive"))
      (node (ref "VR1") (pin "9") (pinfunction "9_9") (pintype "passive"))
    )
    (net (code "29") (name "/SWCLK") (class "Default")
      (node (ref "H6") (pin "2") (pinfunction "2_2") (pintype "passive"))
      (node (ref "U1") (pin "53") (pinfunction "TCK/SWCLK/PB7_53") (pintype "bidirectional"))
    )
    (net (code "30") (name "/SWDIO") (class "Default")
      (node (ref "H6") (pin "4") (pinfunction "4_4") (pintype "passive"))
      (node (ref "U1") (pin "51") (pinfunction "TMS/SWDIO/PB6_51") (pintype "bidirectional"))
    )
    (net (code "31") (name "/USB_DETECT") (class "Default")
      (node (ref "R11") (pin "1") (pinfunction "1_1") (pintype "passive"))
      (node (ref "R13") (pin "2") (pinfunction "2_2") (pintype "passive"))
      (node (ref "U1") (pin "35") (pinfunction "PA5/PGMRDY_35") (pintype "bidirectional"))
    )
    (net (code "32") (name "/X") (class "Default")
      (node (ref "U1") (pin "10") (pinfunction "PA18/PGMD6/AD1_10") (pintype "bidirectional"))
      (node (ref "VR1") (pin "2") (pinfunction "2_2") (pintype "passive"))
    )
    (net (code "33") (name "/Y") (class "Default")
      (node (ref "U1") (pin "13") (pinfunction "PA19/PGMD7/AD2_13") (pintype "bidirectional"))
      (node (ref "VR1") (pin "5") (pinfunction "2'_5") (pintype "passive"))
    )
    (net (code "34") (name "/nRST") (class "Default")
      (node (ref "H6") (pin "1") (pinfunction "1_1") (pintype "passive"))
      (node (ref "S1") (pin "2") (pintype "passive"))
      (node (ref "U1") (pin "39") (pinfunction "NRST_39") (pintype "bidirectional"))
    )
    (net (code "35") (name "3V3") (class "Default")
      (node (ref "C12") (pin "1") (pinfunction "1_1") (pintype "passive"))
      (node (ref "C14") (pin "2") (pinfunction "2_2") (pintype "passive"))
      (node (ref "C15") (pin "1") (pinfunction "1_1") (pintype "passive"))
      (node (ref "C17") (pin "1") (pinfunction "1_1") (pintype "passive"))
      (node (ref "C19") (pin "2") (pinfunction "2_2") (pintype "passive"))
      (node (ref "C21") (pin "1") (pinfunction "1_1") (pintype "passive"))
      (node (ref "C24") (pin "1") (pinfunction "1_1") (pintype "passive"))
      (node (ref "C25") (pin "2") (pinfunction "2_2") (pintype "passive"))
      (node (ref "C28") (pin "1") (pinfunction "1_1") (pintype "passive"))
      (node (ref "C8") (pin "2") (pinfunction "2_2") (pintype "passive"))
      (node (ref "DL1") (pin "2") (pinfunction "A_2") (pintype "passive"))
      (node (ref "DL2") (pin "2") (pinfunction "A_2") (pintype "passive"))
      (node (ref "DL3") (pin "2") (pinfunction "A_2") (pintype "passive"))
      (node (ref "H2") (pin "2") (pinfunction "2_2") (pintype "passive"))
      (node (ref "H6") (pin "7") (pinfunction "7_7") (pintype "passive"))
      (node (ref "H6") (pin "8") (pinfunction "8_8") (pintype "passive"))
      (node (ref "R12") (pin "2") (pinfunction "2_2") (pintype "passive"))
      (node (ref "R7") (pin "2") (pinfunction "2_2") (pintype "passive"))
      (node (ref "R8") (pin "2") (pinfunction "2_2") (pintype "passive"))
      (node (ref "TP10") (pin "1") (pinfunction "TP_1") (pintype "passive"))
      (node (ref "TP11") (pin "1") (pinfunction "TP_1") (pintype "passive"))
      (node (ref "TP12") (pin "1") (pinfunction "TP_1") (pintype "passive"))
      (node (ref "TP14") (pin "1") (pinfunction "TP_1") (pintype "passive"))
      (node (ref "TP15") (pin "1") (pinfunction "TP_1") (pintype "passive"))
      (node (ref "TP16") (pin "1") (pinfunction "TP_1") (pintype "passive"))
      (node (ref "TP22") (pin "1") (pinfunction "TP_1") (pintype "passive"))
      (node (ref "TP24") (pin "1") (pinfunction "TP_1") (pintype "passive"))
      (node (ref "TP4") (pin "1") (pinfunction "1_1") (pintype "passive"))
      (node (ref "TP7") (pin "1") (pinfunction "TP_1") (pintype "passive"))
      (node (ref "U1") (pin "1") (pinfunction "ADVREF_1") (pintype "input"))
      (node (ref "U1") (pin "18") (pinfunction "VDDIO_18") (pintype "power_in"))
      (node (ref "U1") (pin "45") (pinfunction "VDDIO_45") (pintype "power_in"))
      (node (ref "U1") (pin "58") (pinfunction "VDDIO_58") (pintype "power_in"))
      (node (ref "U1") (pin "7") (pinfunction "VDDIN_7") (pintype "power_in"))
      (node (ref "U3") (pin "5") (pinfunction "OUT_5") (pintype "power_in"))
      (node (ref "U5") (pin "1") (pinfunction "RESV_VDDIO_1") (pintype "passive"))
      (node (ref "U5") (pin "13") (pinfunction "VDD_13") (pintype "passive"))
      (node (ref "U5") (pin "22") (pinfunction "nCS_22") (pintype "passive"))
      (node (ref "U5") (pin "8") (pinfunction "VDDIO_8") (pintype "passive"))
      (node (ref "U6") (pin "4") (pinfunction "CSN_4") (pintype "passive"))
      (node (ref "U7") (pin "1") (pinfunction "VCCA_1") (pintype "passive"))
      (node (ref "VR1") (pin "1") (pinfunction "1_1") (pintype "passive"))
      (node (ref "VR1") (pin "4") (pinfunction "1'_4") (pintype "passive"))
    )
    (net (code "36") (name "3V3RF") (class "Default")
      (node (ref "C11") (pin "2") (pinfunction "2_2") (pintype "passive"))
      (node (ref "L2") (pin "2") (pinfunction "2_2") (pintype "passive"))
      (node (ref "TP9") (pin "1") (pinfunction "TP_1") (pintype "passive"))
      (node (ref "U4") (pin "5") (pinfunction "OUT_5") (pintype "power_in"))
    )
    (net (code "37") (name "5V") (class "Default")
      (node (ref "C2") (pin "2") (pintype "passive"))
      (node (ref "C29") (pin "1") (pinfunction "1_1") (pintype "passive"))
      (node (ref "C6") (pin "2") (pinfunction "2_2") (pintype "passive"))
      (node (ref "C9") (pin "2") (pinfunction "2_2") (pintype "passive"))
      (node (ref "H11") (pin "1") (pinfunction "1_1") (pintype "passive"))
      (node (ref "L1") (pin "2") (pintype "passive"))
      (node (ref "TP21") (pin "1") (pinfunction "TP_1") (pintype "passive"))
      (node (ref "TP3") (pin "1") (pinfunction "TP_1") (pintype "passive"))
      (node (ref "TP6") (pin "1") (pinfunction "TP_1") (pintype "passive"))
      (node (ref "TP8") (pin "1") (pinfunction "TP_1") (pintype "passive"))
      (node (ref "U2") (pin "5") (pinfunction "FB_5") (pintype "input"))
      (node (ref "U3") (pin "1") (pinfunction "IN_1") (pintype "power_in"))
      (node (ref "U3") (pin "3") (pinfunction "EN_3") (pintype "input"))
      (node (ref "U4") (pin "1") (pinfunction "IN_1") (pintype "power_in"))
      (node (ref "U4") (pin "3") (pinfunction "EN_3") (pintype "input"))
      (node (ref "U7") (pin "5") (pinfunction "DIR_5") (pintype "passive"))
      (node (ref "U7") (pin "6") (pinfunction "VCCB_6") (pintype "passive"))
    )
    (net (code "38") (name "GND") (class "Default")
      (node (ref "C10") (pin "1") (pinfunction "1_1") (pintype "passive"))
      (node (ref "C11") (pin "1") (pinfunction "1_1") (pintype "passive"))
      (node (ref "C12") (pin "2") (pinfunction "2_2") (pintype "passive"))
      (node (ref "C13") (pin "1") (pinfunction "1_1") (pintype "passive"))
      (node (ref "C14") (pin "1") (pinfunction "1_1") (pintype "passive"))
      (node (ref "C15") (pin "2") (pinfunction "2_2") (pintype "passive"))
      (node (ref "C16") (pin "1") (pinfunction "1_1") (pintype "passive"))
      (node (ref "C17") (pin "2") (pinfunction "2_2") (pintype "passive"))
      (node (ref "C18") (pin "1") (pinfunction "1_1") (pintype "passive"))
      (node (ref "C19") (pin "1") (pinfunction "1_1") (pintype "passive"))
      (node (ref "C2") (pin "1") (pintype "passive"))
      (node (ref "C20") (pin "1") (pinfunction "1_1") (pintype "passive"))
      (node (ref "C21") (pin "2") (pinfunction "2_2") (pintype "passive"))
      (node (ref "C22") (pin "1") (pinfunction "1_1") (pintype "passive"))
      (node (ref "C23") (pin "1") (pinfunction "1_1") (pintype "passive"))
      (node (ref "C24") (pin "2") (pinfunction "2_2") (pintype "passive"))
      (node (ref "C25") (pin "1") (pinfunction "1_1") (pintype "passive"))
      (node (ref "C27") (pin "2") (pinfunction "2_2") (pintype "passive"))
      (node (ref "C28") (pin "2") (pinfunction "2_2") (pintype "passive"))
      (node (ref "C29") (pin "2") (pinfunction "2_2") (pintype "passive"))
      (node (ref "C3") (pin "1") (pinfunction "1_1") (pintype "passive"))
      (node (ref "C4") (pin "1") (pinfunction "1_1") (pintype "passive"))
      (node (ref "C5") (pin "1") (pinfunction "1_1") (pintype "passive"))
      (node (ref "C6") (pin "1") (pinfunction "1_1") (pintype "passive"))
      (node (ref "C7") (pin "1") (pinfunction "1_1") (pintype "passive"))
      (node (ref "C8") (pin "1") (pinfunction "1_1") (pintype "passive"))
      (node (ref "C9") (pin "1") (pinfunction "1_1") (pintype "passive"))
      (node (ref "D1") (pin "1") (pinfunction "A_1") (pintype "passive"))
      (node (ref "GND1") (pin "1") (pinfunction "TP_1") (pintype "passive"))
      (node (ref "GND2") (pin "1") (pinfunction "TP_1") (pintype "passive"))
      (node (ref "H1") (pin "1") (pinfunction "GND_1") (pintype "passive"))
      (node (ref "H1") (pin "3") (pinfunction "GND_3") (pintype "passive"))
      (node (ref "H10") (pin "2") (pinfunction "2_2") (pintype "passive"))
      (node (ref "H11") (pin "3") (pinfunction "3_3") (pintype "passive"))
      (node (ref "H2") (pin "3") (pinfunction "3_3") (pintype "passive"))
      (node (ref "H3") (pin "2") (pinfunction "2_2") (pintype "passive"))
      (node (ref "H3") (pin "4") (pinfunction "4_4") (pintype "passive"))
      (node (ref "H4") (pin "4") (pinfunction "4_4") (pintype "passive"))
      (node (ref "H5") (pin "5") (pinfunction "GND_5") (pintype "passive"))
      (node (ref "H5") (pin "6") (pinfunction "SHLD_6") (pintype "passive"))
      (node (ref "H6") (pin "5") (pinfunction "5_5") (pintype "passive"))
      (node (ref "H6") (pin "6") (pinfunction "6_6") (pintype "passive"))
      (node (ref "H7") (pin "2") (pinfunction "2_2") (pintype "passive"))
      (node (ref "H8") (pin "2") (pinfunction "2_2") (pintype "passive"))
      (node (ref "H9") (pin "2") (pinfunction "2_2") (pintype "passive"))
      (node (ref "Q1") (pin "1") (pinfunction "1_1") (pintype "passive"))
      (node (ref "R10") (pin "1") (pinfunction "1_1") (pintype "passive"))
      (node (ref "R13") (pin "1") (pinfunction "1_1") (pintype "passive"))
      (node (ref "R3") (pin "1") (pinfunction "1_1") (pintype "passive"))
      (node (ref "S1") (pin "1") (pintype "passive"))
      (node (ref "S2") (pin "1") (pintype "passive"))
      (node (ref "U1") (pin "17") (pinfunction "GND_17") (pintype "power_in"))
      (node (ref "U1") (pin "2") (pinfunction "GND_2") (pintype "power_in"))
      (node (ref "U1") (pin "46") (pinfunction "GND_46") (pintype "power_in"))
      (node (ref "U1") (pin "60") (pinfunction "GND_60") (pintype "power_in"))
      (node (ref "U2") (pin "7") (pinfunction "GND_7") (pintype "power_in"))
      (node (ref "U2") (pin "EPAD") (pinfunction "EPAD_EPAD") (pintype "passive"))
      (node (ref "U3") (pin "2") (pinfunction "GND_2") (pintype "power_in"))
      (node (ref "U4") (pin "2") (pinfunction "GND_2") (pintype "power_in"))
      (node (ref "U5") (pin "11") (pinfunction "FSYNC_11") (pintype "passive"))
      (node (ref "U5") (pin "18") (pinfunction "GND_18") (pintype "passive"))
      (node (ref "U5") (pin "20") (pinfunction "RESV_GND_20") (pintype "passive"))
      (node (ref "U5") (pin "9") (pinfunction "AD0/SDO_9") (pintype "passive"))
      (node (ref "U6") (pin "2") (pinfunction "GND_2") (pintype "passive"))
      (node (ref "U7") (pin "2") (pinfunction "GND_2") (pintype "passive"))
      (node (ref "VR1") (pin "10") (pinfunction "10_10") (pintype "passive"))
      (node (ref "VR1") (pin "3") (pinfunction "3_3") (pintype "passive"))
      (node (ref "VR1") (pin "6") (pinfunction "3'_6") (pintype "passive"))
      (node (ref "VR1") (pin "7") (pinfunction "7_7") (pintype "passive"))
    )
    (net (code "39") (name "Net-(C26-Pad1)") (class "Default")
      (node (ref "C26") (pin "1") (pinfunction "1_1") (pintype "passive"))
      (node (ref "R10") (pin "2") (pinfunction "2_2") (pintype "passive"))
    )
    (net (code "40") (name "Net-(D1-K)") (class "Default")
      (node (ref "C1") (pin "1") (pinfunction "1_1") (pintype "passive"))
      (node (ref "D1") (pin "3") (pinfunction "K_3") (pintype "passive"))
      (node (ref "L1") (pin "1") (pintype "passive"))
      (node (ref "TP2") (pin "1") (pinfunction "TP_1") (pintype "passive"))
      (node (ref "U2") (pin "8") (pinfunction "SW_8") (pintype "output"))
    )
    (net (code "41") (name "Net-(DL1-K)") (class "Default")
      (node (ref "DL1") (pin "1") (pinfunction "K_1") (pintype "passive"))
      (node (ref "R6") (pin "1") (pinfunction "1_1") (pintype "passive"))
    )
    (net (code "42") (name "Net-(DL2-K)") (class "Default")
      (node (ref "DL2") (pin "1") (pinfunction "K_1") (pintype "passive"))
      (node (ref "R14") (pin "1") (pinfunction "1_1") (pintype "passive"))
    )
    (net (code "43") (name "Net-(DL3-K)") (class "Default")
      (node (ref "DL3") (pin "1") (pinfunction "K_1") (pintype "passive"))
      (node (ref "R15") (pin "1") (pinfunction "1_1") (pintype "passive"))
    )
    (net (code "44") (name "Net-(F1-Pad2)") (class "Default")
      (node (ref "F1") (pin "2") (pinfunction "2_2") (pintype "passive"))
      (node (ref "Q1") (pin "3") (pinfunction "3_3") (pintype "passive"))
      (node (ref "R1") (pin "2") (pinfunction "2_2") (pintype "passive"))
    )
    (net (code "45") (name "Net-(H1-VBATT)") (class "Default")
      (node (ref "F1") (pin "1") (pinfunction "1_1") (pintype "passive"))
      (node (ref "H1") (pin "2") (pinfunction "VBATT_2") (pintype "passive"))
    )
    (net (code "46") (name "Net-(L2-Pad1)") (class "Default")
      (node (ref "L2") (pin "1") (pinfunction "1_1") (pintype "passive"))
      (node (ref "R9") (pin "2") (pinfunction "2_2") (pintype "passive"))
    )
    (net (code "47") (name "Net-(TP1-TP)") (class "Default")
      (node (ref "C3") (pin "2") (pinfunction "2_2") (pintype "passive"))
      (node (ref "Q1") (pin "2") (pinfunction "2_2") (pintype "passive"))
      (node (ref "R2") (pin "2") (pinfunction "2_2") (pintype "passive"))
      (node (ref "TP1") (pin "1") (pinfunction "TP_1") (pintype "passive"))
      (node (ref "U2") (pin "2") (pinfunction "VIN_2") (pintype "input"))
      (node (ref "U2") (pin "3") (pinfunction "EN_3") (pintype "output"))
    )
    (net (code "48") (name "Net-(TP13-TP)") (class "Default")
      (node (ref "C23") (pin "2") (pinfunction "2_2") (pintype "passive"))
      (node (ref "R9") (pin "1") (pinfunction "1_1") (pintype "passive"))
      (node (ref "TP13") (pin "1") (pinfunction "TP_1") (pintype "passive"))
      (node (ref "U6") (pin "1") (pinfunction "VCC_1") (pintype "passive"))
    )
    (net (code "49") (name "Net-(TP20-TP)") (class "Default")
      (node (ref "H11") (pin "2") (pinfunction "2_2") (pintype "passive"))
      (node (ref "TP20") (pin "1") (pinfunction "TP_1") (pintype "passive"))
      (node (ref "U7") (pin "4") (pinfunction "B_4") (pintype "passive"))
    )
    (net (code "50") (name "Net-(U1A-DDM{slash}PB10)") (class "Default")
      (node (ref "R5") (pin "2") (pinfunction "2_2") (pintype "passive"))
      (node (ref "U1") (pin "56") (pinfunction "DDM/PB10_56") (pintype "bidirectional"))
    )
    (net (code "51") (name "Net-(U1A-DDP{slash}PB11)") (class "Default")
      (node (ref "R4") (pin "2") (pinfunction "2_2") (pintype "passive"))
      (node (ref "U1") (pin "57") (pinfunction "DDP/PB11_57") (pintype "bidirectional"))
    )
    (net (code "52") (name "Net-(U1A-ERASE{slash}PB12)") (class "Default")
      (node (ref "TP5") (pin "1") (pinfunction "1_1") (pintype "passive"))
      (node (ref "U1") (pin "55") (pinfunction "ERASE/PB12_55") (pintype "bidirectional"))
    )
    (net (code "53") (name "Net-(U1A-PB0{slash}AD4)") (class "Default")
      (node (ref "R6") (pin "2") (pinfunction "2_2") (pintype "passive"))
      (node (ref "U1") (pin "3") (pinfunction "PB0/AD4_3") (pintype "bidirectional"))
    )
    (net (code "54") (name "Net-(U1A-XIN{slash}PGMCK{slash}PB9)") (class "Default")
      (node (ref "C4") (pin "2") (pinfunction "2_2") (pintype "passive"))
      (node (ref "U1") (pin "62") (pinfunction "XIN/PGMCK/PB9_62") (pintype "bidirectional"))
      (node (ref "Y1") (pin "2") (pinfunction "OSC2_2") (pintype "passive"))
    )
    (net (code "55") (name "Net-(U1A-XOUT{slash}PB8)") (class "Default")
      (node (ref "C5") (pin "2") (pinfunction "2_2") (pintype "passive"))
      (node (ref "U1") (pin "61") (pinfunction "XOUT/PB8_61") (pintype "bidirectional"))
      (node (ref "Y1") (pin "1") (pinfunction "OSC1_1") (pintype "passive"))
    )
    (net (code "56") (name "Net-(U1B-VDDOUT)") (class "Default")
      (node (ref "C13") (pin "2") (pinfunction "2_2") (pintype "passive"))
      (node (ref "C16") (pin "2") (pinfunction "2_2") (pintype "passive"))
      (node (ref "C18") (pin "2") (pinfunction "2_2") (pintype "passive"))
      (node (ref "C22") (pin "2") (pinfunction "2_2") (pintype "passive"))
      (node (ref "L3") (pin "2") (pinfunction "2_2") (pintype "passive"))
      (node (ref "U1") (pin "12") (pinfunction "VDDCORE_12") (pintype "power_in"))
      (node (ref "U1") (pin "24") (pinfunction "VDDCORE_24") (pintype "power_in"))
      (node (ref "U1") (pin "54") (pinfunction "VDDCORE_54") (pintype "power_in"))
      (node (ref "U1") (pin "8") (pinfunction "VDDOUT_8") (pintype "power_in"))
    )
    (net (code "57") (name "Net-(U1B-VDDPLL)") (class "Default")
      (node (ref "C26") (pin "2") (pinfunction "2_2") (pintype "passive"))
      (node (ref "C27") (pin "1") (pinfunction "1_1") (pintype "passive"))
      (node (ref "L3") (pin "1") (pinfunction "1_1") (pintype "passive"))
      (node (ref "U1") (pin "64") (pinfunction "VDDPLL_64") (pintype "power_in"))
    )
    (net (code "58") (name "Net-(U2-BST)") (class "Default")
      (node (ref "C1") (pin "2") (pinfunction "2_2") (pintype "passive"))
      (node (ref "U2") (pin "1") (pinfunction "BST_1") (pintype "passive"))
    )
    (net (code "59") (name "Net-(U2-PGOOD)") (class "Default")
      (node (ref "R2") (pin "1") (pinfunction "1_1") (pintype "passive"))
      (node (ref "U2") (pin "4") (pinfunction "PGOOD_4") (pintype "output"))
    )
    (net (code "60") (name "Net-(U3-BYP)") (class "Default")
      (node (ref "C7") (pin "2") (pinfunction "2_2") (pintype "passive"))
      (node (ref "U3") (pin "4") (pinfunction "BYP_4") (pintype "passive"))
    )
    (net (code "61") (name "Net-(U4-BYP)") (class "Default")
      (node (ref "C10") (pin "2") (pinfunction "2_2") (pintype "passive"))
      (node (ref "U4") (pin "4") (pinfunction "BYP_4") (pintype "passive"))
    )
    (net (code "62") (name "Net-(U5-REGOUT)") (class "Default")
      (node (ref "C20") (pin "2") (pinfunction "2_2") (pintype "passive"))
      (node (ref "U5") (pin "10") (pinfunction "REGOUT_10") (pintype "passive"))
    )
    (net (code "63") (name "VBUS") (class "Default")
      (node (ref "H5") (pin "1") (pinfunction "VBUS_1") (pintype "power_in"))
      (node (ref "R11") (pin "2") (pinfunction "2_2") (pintype "passive"))
      (node (ref "TP18") (pin "1") (pinfunction "TP_1") (pintype "passive"))
    )
    (net (code "64") (name "unconnected-(H5-ID-Pad4)") (class "Default")
      (node (ref "H5") (pin "4") (pinfunction "ID_4") (pintype "power_in"))
    )
    (net (code "65") (name "unconnected-(H6-Pad3)") (class "Default")
      (node (ref "H6") (pin "3") (pinfunction "3_3") (pintype "passive+no_connect"))
    )
    (net (code "66") (name "unconnected-(H6-Pad9)") (class "Default")
      (node (ref "H6") (pin "9") (pinfunction "9_9") (pintype "passive+no_connect"))
    )
    (net (code "67") (name "unconnected-(H6-Pad10)") (class "Default")
      (node (ref "H6") (pin "10") (pinfunction "10_10") (pintype "passive+no_connect"))
    )
    (net (code "68") (name "unconnected-(U1A-JTAGSEL-Pad50)") (class "Default")
      (node (ref "U1") (pin "50") (pinfunction "JTAGSEL_50") (pintype "input+no_connect"))
    )
    (net (code "69") (name "unconnected-(U1A-PA6{slash}PGMNOE-Pad34)") (class "Default")
      (node (ref "U1") (pin "34") (pinfunction "PA6/PGMNOE_34") (pintype "bidirectional+no_connect"))
    )
    (net (code "70") (name "unconnected-(U1A-PA7{slash}XIN32{slash}PGMNVALID-Pad32)") (class "Default")
      (node (ref "U1") (pin "32") (pinfunction "PA7/XIN32/PGMNVALID_32") (pintype "bidirectional+no_connect"))
    )
    (net (code "71") (name "unconnected-(U1A-PA8{slash}XOUT32{slash}PGMM0-Pad31)") (class "Default")
      (node (ref "U1") (pin "31") (pinfunction "PA8/XOUT32/PGMM0_31") (pintype "bidirectional+no_connect"))
    )
    (net (code "72") (name "unconnected-(U1A-PA9{slash}PGMM1-Pad30)") (class "Default")
      (node (ref "U1") (pin "30") (pinfunction "PA9/PGMM1_30") (pintype "bidirectional+no_connect"))
    )
    (net (code "73") (name "unconnected-(U1A-PA16{slash}PGMD4-Pad19)") (class "Default")
      (node (ref "U1") (pin "19") (pinfunction "PA16/PGMD4_19") (pintype "bidirectional+no_connect"))
    )
    (net (code "74") (name "unconnected-(U1A-PA23{slash}PGMD11-Pad15)") (class "Default")
      (node (ref "U1") (pin "15") (pinfunction "PA23/PGMD11_15") (pintype "bidirectional+no_connect"))
    )
    (net (code "75") (name "unconnected-(U1A-PB13{slash}DAC0-Pad59)") (class "Default")
      (node (ref "U1") (pin "59") (pinfunction "PB13/DAC0_59") (pintype "bidirectional+no_connect"))
    )
    (net (code "76") (name "unconnected-(U1A-PB14{slash}DAC1-Pad63)") (class "Default")
      (node (ref "U1") (pin "63") (pinfunction "PB14/DAC1_63") (pintype "bidirectional+no_connect"))
    )
    (net (code "77") (name "unconnected-(U1A-TDI{slash}PB4-Pad33)") (class "Default")
      (node (ref "U1") (pin "33") (pinfunction "TDI/PB4_33") (pintype "bidirectional+no_connect"))
    )
    (net (code "78") (name "unconnected-(U1A-TDO{slash}TRACESWO{slash}PB5-Pad49)") (class "Default")
      (node (ref "U1") (pin "49") (pinfunction "TDO/TRACESWO/PB5_49") (pintype "bidirectional+no_connect"))
    )
    (net (code "79") (name "unconnected-(U1A-TST-Pad40)") (class "Default")
      (node (ref "U1") (pin "40") (pinfunction "TST_40") (pintype "input+no_connect"))
    )
    (net (code "80") (name "unconnected-(U2-NC-Pad6)") (class "Default")
      (node (ref "U2") (pin "6") (pinfunction "NC_6") (pintype "passive+no_connect"))
    )
    (net (code "81") (name "unconnected-(U5-AUX_CL-Pad7)") (class "Default")
      (node (ref "U5") (pin "7") (pinfunction "AUX_CL_7") (pintype "passive+no_connect"))
    )
    (net (code "82") (name "unconnected-(U5-AUX_DA-Pad21)") (class "Default")
      (node (ref "U5") (pin "21") (pinfunction "AUX_DA_21") (pintype "passive+no_connect"))
    )
    (net (code "83") (name "unconnected-(U5-INT-Pad12)") (class "Default")
      (node (ref "U5") (pin "12") (pinfunction "INT_12") (pintype "passive"))
    )
  )
)
